# Port_K_Output_Port.net
KiCad netlist of a schematic drawn in Altium Designer
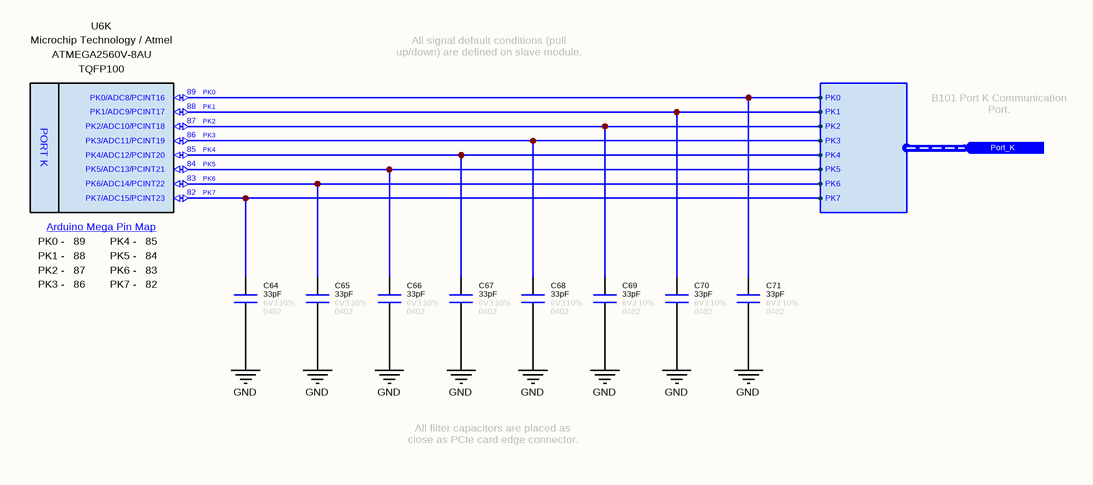
[diagram p0: Port K Output Port.SchDoc]

(export (version "E")
  (design (tool "Eeschema 10.0.6"))
  (components
    (comp (ref "C64")
      (value "33pF")
      (footprint "CAPACITOR_0402")
      (description "Capacitor - 33pF [0402] (Ceramic)")
      (fields
        (field (name "MANUFACTURER PART NUMBER") "C0402C330J9RACAUTO")
        (field (name "TOLERANCE") "10%")
        (field (name "CASE") "0402")
        (field (name "VOLTAGE") "6V3")
      )
      (libsource (lib "P101DA_Library") (part "Capacitor - 33pF [0402-6V3]"))
    )
    (comp (ref "C65")
      (value "33pF")
      (footprint "CAPACITOR_0402")
      (description "Capacitor - 33pF [0402] (Ceramic)")
      (fields
        (field (name "MANUFACTURER PART NUMBER") "C0402C330J9RACAUTO")
        (field (name "TOLERANCE") "10%")
        (field (name "CASE") "0402")
        (field (name "VOLTAGE") "6V3")
      )
      (libsource (lib "P101DA_Library") (part "Capacitor - 33pF [0402-6V3]"))
    )
    (comp (ref "C66")
      (value "33pF")
      (footprint "CAPACITOR_0402")
      (description "Capacitor - 33pF [0402] (Ceramic)")
      (fields
        (field (name "MANUFACTURER PART NUMBER") "C0402C330J9RACAUTO")
        (field (name "TOLERANCE") "10%")
        (field (name "CASE") "0402")
        (field (name "VOLTAGE") "6V3")
      )
      (libsource (lib "P101DA_Library") (part "Capacitor - 33pF [0402-6V3]"))
    )
    (comp (ref "C67")
      (value "33pF")
      (footprint "CAPACITOR_0402")
      (description "Capacitor - 33pF [0402] (Ceramic)")
      (fields
        (field (name "MANUFACTURER PART NUMBER") "C0402C330J9RACAUTO")
        (field (name "TOLERANCE") "10%")
        (field (name "CASE") "0402")
        (field (name "VOLTAGE") "6V3")
      )
      (libsource (lib "P101DA_Library") (part "Capacitor - 33pF [0402-6V3]"))
    )
    (comp (ref "C68")
      (value "33pF")
      (footprint "CAPACITOR_0402")
      (description "Capacitor - 33pF [0402] (Ceramic)")
      (fields
        (field (name "MANUFACTURER PART NUMBER") "C0402C330J9RACAUTO")
        (field (name "TOLERANCE") "10%")
        (field (name "CASE") "0402")
        (field (name "VOLTAGE") "6V3")
      )
      (libsource (lib "P101DA_Library") (part "Capacitor - 33pF [0402-6V3]"))
    )
    (comp (ref "C69")
      (value "33pF")
      (footprint "CAPACITOR_0402")
      (description "Capacitor - 33pF [0402] (Ceramic)")
      (fields
        (field (name "MANUFACTURER PART NUMBER") "C0402C330J9RACAUTO")
        (field (name "TOLERANCE") "10%")
        (field (name "CASE") "0402")
        (field (name "VOLTAGE") "6V3")
      )
      (libsource (lib "P101DA_Library") (part "Capacitor - 33pF [0402-6V3]"))
    )
    (comp (ref "C70")
      (value "33pF")
      (footprint "CAPACITOR_0402")
      (description "Capacitor - 33pF [0402] (Ceramic)")
      (fields
        (field (name "MANUFACTURER PART NUMBER") "C0402C330J9RACAUTO")
        (field (name "TOLERANCE") "10%")
        (field (name "CASE") "0402")
        (field (name "VOLTAGE") "6V3")
      )
      (libsource (lib "P101DA_Library") (part "Capacitor - 33pF [0402-6V3]"))
    )
    (comp (ref "C71")
      (value "33pF")
      (footprint "CAPACITOR_0402")
      (description "Capacitor - 33pF [0402] (Ceramic)")
      (fields
        (field (name "MANUFACTURER PART NUMBER") "C0402C330J9RACAUTO")
        (field (name "TOLERANCE") "10%")
        (field (name "CASE") "0402")
        (field (name "VOLTAGE") "6V3")
      )
      (libsource (lib "P101DA_Library") (part "Capacitor - 33pF [0402-6V3]"))
    )
    (comp (ref "U6")
      (value "ATMEGA2560V-8AU")
      (footprint "TQFP-100")
      (description "ATmega Series 256 KB Flash 8 KB SRAM 8 MHz 8-Bit Microcontroller - TQFP-100")
      (fields
        (field (name "MANUFACTURER NAME") "Microchip Technology / Atmel")
        (field (name "MANUFACTURER PART NUMBER") "ATMEGA2560V-8AU")
        (field (name "CASE") "TQFP100")
      )
      (libsource (lib "P101DA_Library") (part "IC - AtMega2560V-8AU"))
    )
  )
  (nets
    (net (code "2") (name "/PK0") (class "Default")
      (node (ref "C71") (pin "2") (pinfunction "2_2") (pintype "passive"))
      (node (ref "U6") (pin "89") (pinfunction "PK0/ADC8/PCINT16_89") (pintype "bidirectional"))
    )
    (net (code "3") (name "/PK1") (class "Default")
      (node (ref "C70") (pin "2") (pinfunction "2_2") (pintype "passive"))
      (node (ref "U6") (pin "88") (pinfunction "PK1/ADC9/PCINT17_88") (pintype "bidirectional"))
    )
    (net (code "4") (name "/PK2") (class "Default")
      (node (ref "C69") (pin "2") (pinfunction "2_2") (pintype "passive"))
      (node (ref "U6") (pin "87") (pinfunction "PK2/ADC10/PCINT18_87") (pintype "bidirectional"))
    )
    (net (code "5") (name "/PK3") (class "Default")
      (node (ref "C68") (pin "2") (pinfunction "2_2") (pintype "passive"))
      (node (ref "U6") (pin "86") (pinfunction "PK3/ADC11/PCINT19_86") (pintype "bidirectional"))
    )
    (net (code "6") (name "/PK4") (class "Default")
      (node (ref "C67") (pin "2") (pinfunction "2_2") (pintype "passive"))
      (node (ref "U6") (pin "85") (pinfunction "PK4/ADC12/PCINT20_85") (pintype "bidirectional"))
    )
    (net (code "7") (name "/PK5") (class "Default")
      (node (ref "C66") (pin "2") (pinfunction "2_2") (pintype "passive"))
      (node (ref "U6") (pin "84") (pinfunction "PK5/ADC13/PCINT21_84") (pintype "bidirectional"))
    )
    (net (code "8") (name "/PK6") (class "Default")
      (node (ref "C65") (pin "2") (pinfunction "2_2") (pintype "passive"))
      (node (ref "U6") (pin "83") (pinfunction "PK6/ADC14/PCINT22_83") (pintype "bidirectional"))
    )
    (net (code "9") (name "/PK7") (class "Default")
      (node (ref "C64") (pin "2") (pinfunction "2_2") (pintype "passive"))
      (node (ref "U6") (pin "82") (pinfunction "PK7/ADC15/PCINT23_82") (pintype "bidirectional"))
    )
    (net (code "11") (name "GND") (class "Default")
      (node (ref "C64") (pin "1") (pinfunction "1_1") (pintype "passive"))
      (node (ref "C65") (pin "1") (pinfunction "1_1") (pintype "passive"))
      (node (ref "C66") (pin "1") (pinfunction "1_1") (pintype "passive"))
      (node (ref "C67") (pin "1") (pinfunction "1_1") (pintype "passive"))
      (node (ref "C68") (pin "1") (pinfunction "1_1") (pintype "passive"))
      (node (ref "C69") (pin "1") (pinfunction "1_1") (pintype "passive"))
      (node (ref "C70") (pin "1") (pinfunction "1_1") (pintype "passive"))
      (node (ref "C71") (pin "1") (pinfunction "1_1") (pintype "passive"))
    )
  )
)
